# Smartwatch-EXTRA-BOTTOM.net
KiCad netlist of a schematic drawn in EAGLE
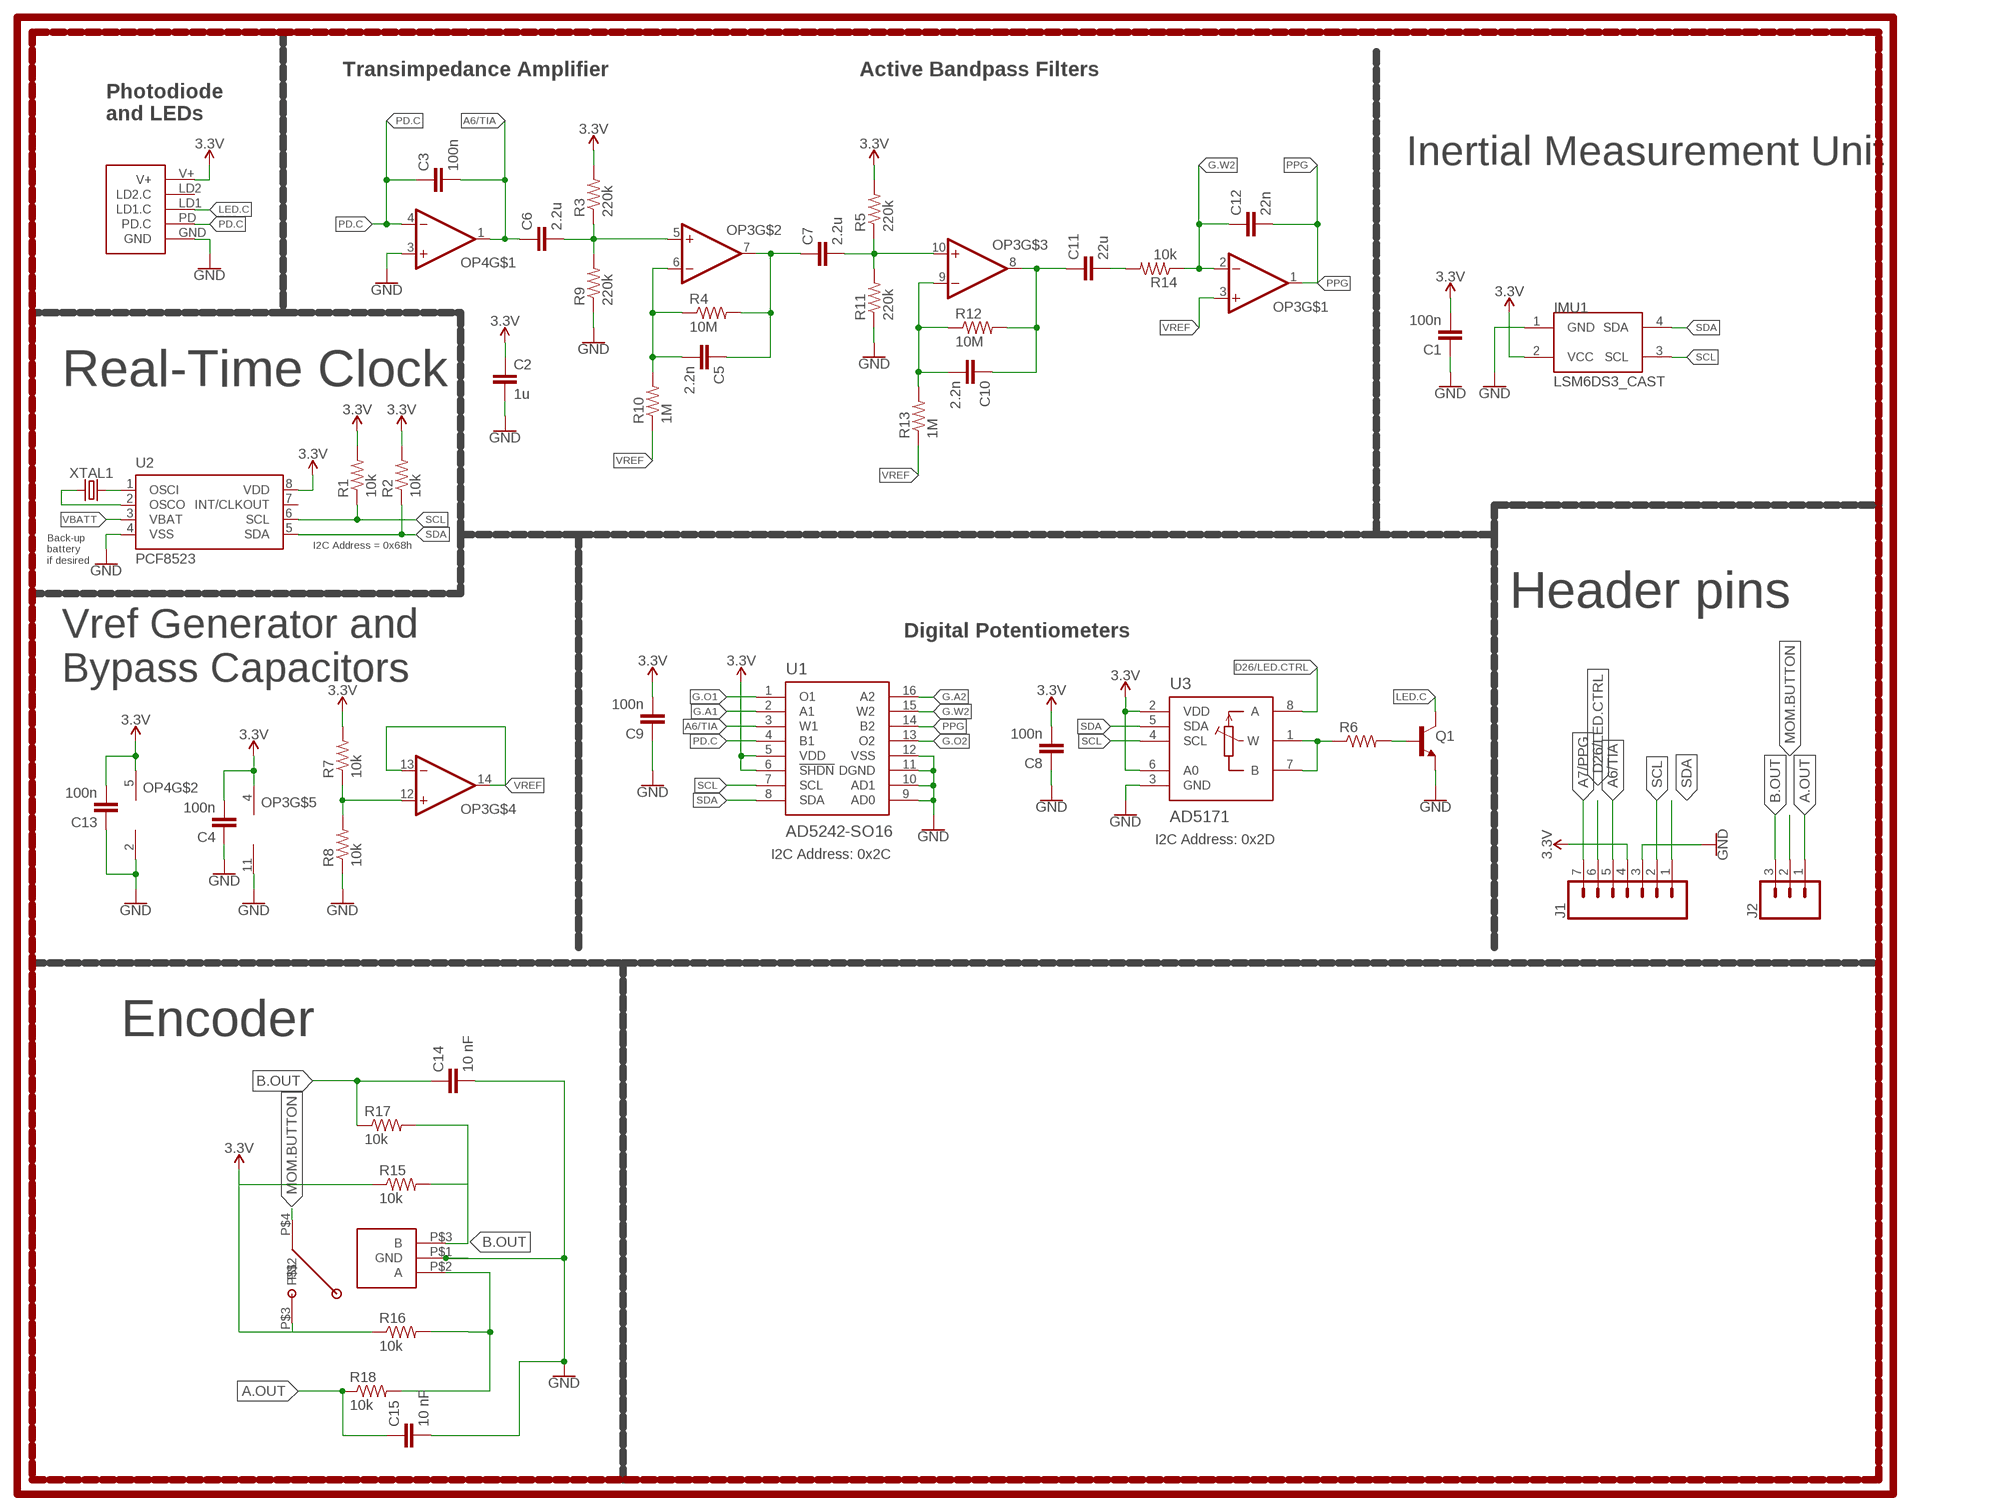
[diagram p0: schematic, sheet 1]

(export (version "E")
  (design (tool "Eeschema 10.0.6"))
  (components
    (comp (ref "B1")
      (value "SWITCH")
      (footprint "eagle-import:SWITCH")
      (libsource (lib "eagle-import") (part "SWITCH"))
    )
    (comp (ref "C1")
      (value "100n")
      (footprint "eagle-import:C0603")
      (libsource (lib "eagle-import") (part "CAPACITOR0603"))
    )
    (comp (ref "C2")
      (value "1u")
      (footprint "eagle-import:C0603")
      (libsource (lib "eagle-import") (part "CAPACITOR0603"))
    )
    (comp (ref "C3")
      (value "100n")
      (footprint "eagle-import:C0603")
      (libsource (lib "eagle-import") (part "CAPACITOR0603"))
    )
    (comp (ref "C4")
      (value "100n")
      (footprint "eagle-import:C0603")
      (libsource (lib "eagle-import") (part "CAPACITOR0603"))
    )
    (comp (ref "C5")
      (value "2.2n")
      (footprint "eagle-import:C0603")
      (libsource (lib "eagle-import") (part "CAPACITOR0603"))
    )
    (comp (ref "C6")
      (value "2.2u")
      (footprint "eagle-import:C0603")
      (libsource (lib "eagle-import") (part "CAPACITOR0603"))
    )
    (comp (ref "C7")
      (value "2.2u")
      (footprint "eagle-import:C0603")
      (libsource (lib "eagle-import") (part "CAPACITOR0603"))
    )
    (comp (ref "C8")
      (value "100n")
      (footprint "eagle-import:C0603")
      (libsource (lib "eagle-import") (part "CAPACITOR0603"))
    )
    (comp (ref "C9")
      (value "100n")
      (footprint "eagle-import:C0603")
      (libsource (lib "eagle-import") (part "CAPACITOR0603"))
    )
    (comp (ref "C10")
      (value "2.2n")
      (footprint "eagle-import:C0603")
      (libsource (lib "eagle-import") (part "CAPACITOR0603"))
    )
    (comp (ref "C11")
      (value "22u")
      (footprint "eagle-import:C0603")
      (libsource (lib "eagle-import") (part "CAPACITOR0603"))
    )
    (comp (ref "C12")
      (value "22n")
      (footprint "eagle-import:C0603")
      (libsource (lib "eagle-import") (part "CAPACITOR0603"))
    )
    (comp (ref "C13")
      (value "100n")
      (footprint "eagle-import:C0603")
      (libsource (lib "eagle-import") (part "CAPACITOR0603"))
    )
    (comp (ref "C14")
      (value "10 nF")
      (footprint "eagle-import:C0603")
      (libsource (lib "eagle-import") (part "CAPACITOR0603"))
    )
    (comp (ref "C15")
      (value "10 nF")
      (footprint "eagle-import:C0603")
      (libsource (lib "eagle-import") (part "CAPACITOR0603"))
    )
    (comp (ref "ENC1")
      (value "EVQVU")
      (footprint "eagle-import:EVQVU")
      (libsource (lib "eagle-import") (part "EVQVU"))
    )
    (comp (ref "IMU1")
      (value "LSM6DS3_CAST")
      (footprint "eagle-import:LSM6DS3_CAST")
      (libsource (lib "eagle-import") (part "LSM6DS3_CAST"))
    )
    (comp (ref "J1")
      (value "CONN_07-1.27MM")
      (footprint "eagle-import:1X07_1.27MM")
      (libsource (lib "eagle-import") (part "CONN_07-1.27MM"))
    )
    (comp (ref "J2")
      (value "CONN_03.50MIL")
      (footprint "eagle-import:1X03_1.27MM")
      (libsource (lib "eagle-import") (part "CONN_03.50MIL"))
    )
    (comp (ref "OP3")
      (value "OP-QUAD-SO14")
      (footprint "eagle-import:SO14")
      (libsource (lib "eagle-import") (part "OP-QUAD-SO14"))
    )
    (comp (ref "OP4")
      (value "OP-SINGLEOT")
      (footprint "eagle-import:SOT23-5")
      (libsource (lib "eagle-import") (part "OP-SINGLEOT"))
    )
    (comp (ref "Q1")
      (value "NPN-GENERIC")
      (footprint "eagle-import:SOT23-3")
      (libsource (lib "eagle-import") (part "NPN-GENERIC"))
    )
    (comp (ref "R1")
      (value "10k")
      (footprint "eagle-import:R0603")
      (libsource (lib "eagle-import") (part "RESISTOR0603"))
    )
    (comp (ref "R2")
      (value "10k")
      (footprint "eagle-import:R0603")
      (libsource (lib "eagle-import") (part "RESISTOR0603"))
    )
    (comp (ref "R3")
      (value "220k")
      (footprint "eagle-import:R0603")
      (libsource (lib "eagle-import") (part "RESISTOR0603"))
    )
    (comp (ref "R4")
      (value "10M")
      (footprint "eagle-import:R0603")
      (libsource (lib "eagle-import") (part "RESISTOR0603"))
    )
    (comp (ref "R5")
      (value "220k")
      (footprint "eagle-import:R0603")
      (libsource (lib "eagle-import") (part "RESISTOR0603"))
    )
    (comp (ref "R6")
      (value "RESISTOR0603")
      (footprint "eagle-import:R0603")
      (libsource (lib "eagle-import") (part "RESISTOR0603"))
    )
    (comp (ref "R7")
      (value "10k")
      (footprint "eagle-import:R0402")
      (libsource (lib "eagle-import") (part "RESISTOR0402"))
    )
    (comp (ref "R8")
      (value "10k")
      (footprint "eagle-import:R0402")
      (libsource (lib "eagle-import") (part "RESISTOR0402"))
    )
    (comp (ref "R9")
      (value "220k")
      (footprint "eagle-import:R0603")
      (libsource (lib "eagle-import") (part "RESISTOR0603"))
    )
    (comp (ref "R10")
      (value "1M")
      (footprint "eagle-import:R0603")
      (libsource (lib "eagle-import") (part "RESISTOR0603"))
    )
    (comp (ref "R11")
      (value "220k")
      (footprint "eagle-import:R0603")
      (libsource (lib "eagle-import") (part "RESISTOR0603"))
    )
    (comp (ref "R12")
      (value "10M")
      (footprint "eagle-import:R0603")
      (libsource (lib "eagle-import") (part "RESISTOR0603"))
    )
    (comp (ref "R13")
      (value "1M")
      (footprint "eagle-import:R0603")
      (libsource (lib "eagle-import") (part "RESISTOR0603"))
    )
    (comp (ref "R14")
      (value "10k")
      (footprint "eagle-import:R0603")
      (libsource (lib "eagle-import") (part "RESISTOR0603"))
    )
    (comp (ref "R15")
      (value "10k")
      (footprint "eagle-import:R0603")
      (libsource (lib "eagle-import") (part "RESISTOR0603"))
    )
    (comp (ref "R16")
      (value "10k")
      (footprint "eagle-import:R0603")
      (libsource (lib "eagle-import") (part "RESISTOR0603"))
    )
    (comp (ref "R17")
      (value "10k")
      (footprint "eagle-import:R0603")
      (libsource (lib "eagle-import") (part "RESISTOR0603"))
    )
    (comp (ref "R18")
      (value "10k")
      (footprint "eagle-import:R0603")
      (libsource (lib "eagle-import") (part "RESISTOR0603"))
    )
    (comp (ref "U1")
      (value "AD5242-SO16")
      (footprint "eagle-import:SO16")
      (libsource (lib "eagle-import") (part "AD5242-SO16"))
    )
    (comp (ref "U2")
      (value "PCF8523")
      (footprint "eagle-import:SO8")
      (libsource (lib "eagle-import") (part "PCF8523"))
    )
    (comp (ref "U3")
      (value "AD5171")
      (footprint "eagle-import:SOT-23-8")
      (libsource (lib "eagle-import") (part "AD5171"))
    )
    (comp (ref "U4")
      (value "PPG.MODULE.2")
      (footprint "eagle-import:PPG.MODULE.2")
      (libsource (lib "eagle-import") (part "PPG.MODULE.2"))
    )
    (comp (ref "XTAL1")
      (value "32.7680kHz")
      (footprint "eagle-import:2-SMD.NOLEAD.2.0MMTO1.2MM")
      (fields (field (name "FREQ") "32.7680KHZ"))
      (libsource (lib "eagle-import") (part "CRYSTALECS-.327-12.5-12-C-TR"))
    )
  )
  (nets
    (net (code "1") (name "3.3V") (class "Default")
      (node (ref "B1") (pin "P$3") (pinfunction "P$2_P$3") (pintype "bidirectional"))
      (node (ref "C1") (pin "2") (pinfunction "2_2") (pintype "passive"))
      (node (ref "C13") (pin "2") (pinfunction "2_2") (pintype "passive"))
      (node (ref "C2") (pin "1") (pinfunction "1_1") (pintype "passive"))
      (node (ref "C4") (pin "2") (pinfunction "2_2") (pintype "passive"))
      (node (ref "C8") (pin "2") (pinfunction "2_2") (pintype "passive"))
      (node (ref "C9") (pin "2") (pinfunction "2_2") (pintype "passive"))
      (node (ref "IMU1") (pin "2") (pinfunction "VCC_2") (pintype "bidirectional"))
      (node (ref "J1") (pin "4") (pinfunction "4_4") (pintype "passive"))
      (node (ref "OP3") (pin "4") (pinfunction "V+_4") (pintype "power_in"))
      (node (ref "OP4") (pin "5") (pinfunction "V+_5") (pintype "power_in"))
      (node (ref "R1") (pin "2") (pinfunction "2_2") (pintype "passive"))
      (node (ref "R15") (pin "1") (pinfunction "1_1") (pintype "passive"))
      (node (ref "R16") (pin "1") (pinfunction "1_1") (pintype "passive"))
      (node (ref "R2") (pin "2") (pinfunction "2_2") (pintype "passive"))
      (node (ref "R3") (pin "2") (pinfunction "2_2") (pintype "passive"))
      (node (ref "R5") (pin "2") (pinfunction "2_2") (pintype "passive"))
      (node (ref "R7") (pin "2") (pinfunction "2_2") (pintype "passive"))
      (node (ref "U1") (pin "5") (pinfunction "VDD_5") (pintype "bidirectional"))
      (node (ref "U1") (pin "6") (pinfunction "~{SHDN}_6") (pintype "bidirectional"))
      (node (ref "U2") (pin "8") (pinfunction "VDD_8") (pintype "power_in"))
      (node (ref "U3") (pin "2") (pinfunction "VDD_2") (pintype "bidirectional"))
      (node (ref "U3") (pin "6") (pinfunction "A0_6") (pintype "bidirectional"))
      (node (ref "U4") (pin "V+") (pinfunction "V+_V+") (pintype "bidirectional"))
    )
    (net (code "2") (name "A.OUT") (class "Default")
      (node (ref "C15") (pin "1") (pinfunction "1_1") (pintype "passive"))
      (node (ref "ENC1") (pin "P$2") (pinfunction "A_P$2") (pintype "bidirectional"))
      (node (ref "J2") (pin "1") (pinfunction "1_1") (pintype "passive"))
      (node (ref "R16") (pin "2") (pinfunction "2_2") (pintype "passive"))
      (node (ref "R18") (pin "1") (pinfunction "1_1") (pintype "passive"))
      (node (ref "R18") (pin "2") (pinfunction "2_2") (pintype "passive"))
    )
    (net (code "3") (name "A6{slash}TIA") (class "Default")
      (node (ref "C3") (pin "2") (pinfunction "2_2") (pintype "passive"))
      (node (ref "C6") (pin "1") (pinfunction "1_1") (pintype "passive"))
      (node (ref "J1") (pin "5") (pinfunction "5_5") (pintype "passive"))
      (node (ref "OP4") (pin "1") (pinfunction "OUT_1") (pintype "output"))
      (node (ref "U1") (pin "3") (pinfunction "W1_3") (pintype "bidirectional"))
    )
    (net (code "4") (name "A7{slash}PPG") (class "Default")
      (node (ref "J1") (pin "7") (pinfunction "7_7") (pintype "passive"))
    )
    (net (code "5") (name "B.OUT") (class "Default")
      (node (ref "C14") (pin "1") (pinfunction "1_1") (pintype "passive"))
      (node (ref "ENC1") (pin "P$3") (pinfunction "B_P$3") (pintype "bidirectional"))
      (node (ref "J2") (pin "3") (pinfunction "3_3") (pintype "passive"))
      (node (ref "R17") (pin "1") (pinfunction "1_1") (pintype "passive"))
    )
    (net (code "6") (name "D26{slash}LED.CTRL") (class "Default")
      (node (ref "J1") (pin "6") (pinfunction "6_6") (pintype "passive"))
      (node (ref "U3") (pin "8") (pinfunction "A_8") (pintype "bidirectional"))
    )
    (net (code "7") (name "G.A1") (class "Default")
      (node (ref "U1") (pin "2") (pinfunction "A1_2") (pintype "bidirectional"))
    )
    (net (code "8") (name "G.A2") (class "Default")
      (node (ref "U1") (pin "16") (pinfunction "A2_16") (pintype "bidirectional"))
    )
    (net (code "9") (name "G.O1") (class "Default")
      (node (ref "U1") (pin "1") (pinfunction "O1_1") (pintype "bidirectional"))
    )
    (net (code "10") (name "G.O2") (class "Default")
      (node (ref "U1") (pin "13") (pinfunction "O2_13") (pintype "bidirectional"))
    )
    (net (code "11") (name "G.W2") (class "Default")
      (node (ref "C12") (pin "1") (pinfunction "1_1") (pintype "passive"))
      (node (ref "OP3") (pin "2") (pinfunction "-IN_2") (pintype "input"))
      (node (ref "R14") (pin "1") (pinfunction "1_1") (pintype "passive"))
      (node (ref "U1") (pin "15") (pinfunction "W2_15") (pintype "bidirectional"))
    )
    (net (code "12") (name "GND") (class "Default")
      (node (ref "C1") (pin "1") (pinfunction "1_1") (pintype "passive"))
      (node (ref "C13") (pin "1") (pinfunction "1_1") (pintype "passive"))
      (node (ref "C14") (pin "2") (pinfunction "2_2") (pintype "passive"))
      (node (ref "C15") (pin "2") (pinfunction "2_2") (pintype "passive"))
      (node (ref "C2") (pin "2") (pinfunction "2_2") (pintype "passive"))
      (node (ref "C4") (pin "1") (pinfunction "1_1") (pintype "passive"))
      (node (ref "C8") (pin "1") (pinfunction "1_1") (pintype "passive"))
      (node (ref "C9") (pin "1") (pinfunction "1_1") (pintype "passive"))
      (node (ref "ENC1") (pin "P$1") (pinfunction "GND_P$1") (pintype "bidirectional"))
      (node (ref "IMU1") (pin "1") (pinfunction "GND_1") (pintype "bidirectional"))
      (node (ref "J1") (pin "3") (pinfunction "3_3") (pintype "passive"))
      (node (ref "OP3") (pin "11") (pinfunction "V-_11") (pintype "power_in"))
      (node (ref "OP4") (pin "2") (pinfunction "V-_2") (pintype "power_in"))
      (node (ref "OP4") (pin "3") (pinfunction "+IN_3") (pintype "input"))
      (node (ref "Q1") (pin "2") (pinfunction "E_2") (pintype "passive"))
      (node (ref "R11") (pin "1") (pinfunction "1_1") (pintype "passive"))
      (node (ref "R8") (pin "1") (pinfunction "1_1") (pintype "passive"))
      (node (ref "R9") (pin "1") (pinfunction "1_1") (pintype "passive"))
      (node (ref "U1") (pin "10") (pinfunction "AD1_10") (pintype "bidirectional"))
      (node (ref "U1") (pin "11") (pinfunction "DGND_11") (pintype "bidirectional"))
      (node (ref "U1") (pin "12") (pinfunction "VSS_12") (pintype "bidirectional"))
      (node (ref "U1") (pin "9") (pinfunction "AD0_9") (pintype "bidirectional"))
      (node (ref "U2") (pin "4") (pinfunction "VSS_4") (pintype "power_in"))
      (node (ref "U3") (pin "3") (pinfunction "GND_3") (pintype "bidirectional"))
      (node (ref "U4") (pin "GND") (pinfunction "GND_GND") (pintype "bidirectional"))
    )
    (net (code "13") (name "LED.C") (class "Default")
      (node (ref "Q1") (pin "3") (pinfunction "C_3") (pintype "passive"))
      (node (ref "U4") (pin "LD1") (pinfunction "LD1.C_LD1") (pintype "bidirectional"))
    )
    (net (code "14") (name "MOM.BUTTON") (class "Default")
      (node (ref "B1") (pin "P$4") (pinfunction "P$1_P$4") (pintype "bidirectional"))
      (node (ref "J2") (pin "2") (pinfunction "2_2") (pintype "passive"))
    )
    (net (code "15") (name "Net-(C11-Pad2)") (class "Default")
      (node (ref "C11") (pin "2") (pinfunction "2_2") (pintype "passive"))
      (node (ref "R14") (pin "2") (pinfunction "2_2") (pintype "passive"))
    )
    (net (code "16") (name "Net-(OP3B-+IN)") (class "Default")
      (node (ref "C6") (pin "2") (pinfunction "2_2") (pintype "passive"))
      (node (ref "OP3") (pin "5") (pinfunction "+IN_5") (pintype "input"))
      (node (ref "R3") (pin "1") (pinfunction "1_1") (pintype "passive"))
      (node (ref "R9") (pin "2") (pinfunction "2_2") (pintype "passive"))
    )
    (net (code "17") (name "Net-(OP3B--IN)") (class "Default")
      (node (ref "C5") (pin "2") (pinfunction "2_2") (pintype "passive"))
      (node (ref "OP3") (pin "6") (pinfunction "-IN_6") (pintype "input"))
      (node (ref "R10") (pin "2") (pinfunction "2_2") (pintype "passive"))
      (node (ref "R4") (pin "1") (pinfunction "1_1") (pintype "passive"))
    )
    (net (code "18") (name "Net-(OP3B-OUT)") (class "Default")
      (node (ref "C5") (pin "1") (pinfunction "1_1") (pintype "passive"))
      (node (ref "C7") (pin "1") (pinfunction "1_1") (pintype "passive"))
      (node (ref "OP3") (pin "7") (pinfunction "OUT_7") (pintype "output"))
      (node (ref "R4") (pin "2") (pinfunction "2_2") (pintype "passive"))
    )
    (net (code "19") (name "Net-(OP3C-+IN)") (class "Default")
      (node (ref "C7") (pin "2") (pinfunction "2_2") (pintype "passive"))
      (node (ref "OP3") (pin "10") (pinfunction "+IN_10") (pintype "input"))
      (node (ref "R11") (pin "2") (pinfunction "2_2") (pintype "passive"))
      (node (ref "R5") (pin "1") (pinfunction "1_1") (pintype "passive"))
    )
    (net (code "20") (name "Net-(OP3C--IN)") (class "Default")
      (node (ref "C10") (pin "2") (pinfunction "2_2") (pintype "passive"))
      (node (ref "OP3") (pin "9") (pinfunction "-IN_9") (pintype "input"))
      (node (ref "R12") (pin "1") (pinfunction "1_1") (pintype "passive"))
      (node (ref "R13") (pin "2") (pinfunction "2_2") (pintype "passive"))
    )
    (net (code "21") (name "Net-(OP3C-OUT)") (class "Default")
      (node (ref "C10") (pin "1") (pinfunction "1_1") (pintype "passive"))
      (node (ref "C11") (pin "1") (pinfunction "1_1") (pintype "passive"))
      (node (ref "OP3") (pin "8") (pinfunction "OUT_8") (pintype "output"))
      (node (ref "R12") (pin "2") (pinfunction "2_2") (pintype "passive"))
    )
    (net (code "22") (name "Net-(OP3D-+IN)") (class "Default")
      (node (ref "OP3") (pin "12") (pinfunction "+IN_12") (pintype "input"))
      (node (ref "R7") (pin "1") (pinfunction "1_1") (pintype "passive"))
      (node (ref "R8") (pin "2") (pinfunction "2_2") (pintype "passive"))
    )
    (net (code "23") (name "Net-(Q1-B)") (class "Default")
      (node (ref "Q1") (pin "1") (pinfunction "B_1") (pintype "passive"))
      (node (ref "R6") (pin "2") (pinfunction "2_2") (pintype "passive"))
    )
    (net (code "24") (name "Net-(R15-Pad2)") (class "Default")
      (node (ref "R15") (pin "2") (pinfunction "2_2") (pintype "passive"))
      (node (ref "R17") (pin "2") (pinfunction "2_2") (pintype "passive"))
    )
    (net (code "25") (name "Net-(U2-OSCI)") (class "Default")
      (node (ref "U2") (pin "1") (pinfunction "OSCI_1") (pintype "bidirectional"))
      (node (ref "XTAL1") (pin "P$2") (pinfunction "2_P$2") (pintype "passive"))
    )
    (net (code "26") (name "Net-(U2-OSCO)") (class "Default")
      (node (ref "U2") (pin "2") (pinfunction "OSCO_2") (pintype "bidirectional"))
      (node (ref "XTAL1") (pin "P$1") (pinfunction "1_P$1") (pintype "passive"))
    )
    (net (code "27") (name "Net-(U3-B)") (class "Default")
      (node (ref "R6") (pin "1") (pinfunction "1_1") (pintype "passive"))
      (node (ref "U3") (pin "1") (pinfunction "W_1") (pintype "bidirectional"))
      (node (ref "U3") (pin "7") (pinfunction "B_7") (pintype "bidirectional"))
    )
    (net (code "28") (name "PD.C") (class "Default")
      (node (ref "C3") (pin "1") (pinfunction "1_1") (pintype "passive"))
      (node (ref "OP4") (pin "4") (pinfunction "-IN_4") (pintype "input"))
      (node (ref "U1") (pin "4") (pinfunction "B1_4") (pintype "bidirectional"))
      (node (ref "U4") (pin "PD") (pinfunction "PD.C_PD") (pintype "bidirectional"))
    )
    (net (code "29") (name "PPG") (class "Default")
      (node (ref "C12") (pin "2") (pinfunction "2_2") (pintype "passive"))
      (node (ref "OP3") (pin "1") (pinfunction "OUT_1") (pintype "output"))
      (node (ref "U1") (pin "14") (pinfunction "B2_14") (pintype "bidirectional"))
    )
    (net (code "30") (name "SCL") (class "Default")
      (node (ref "IMU1") (pin "3") (pinfunction "SCL_3") (pintype "bidirectional"))
      (node (ref "J1") (pin "2") (pinfunction "2_2") (pintype "passive"))
      (node (ref "R1") (pin "1") (pinfunction "1_1") (pintype "passive"))
      (node (ref "U1") (pin "7") (pinfunction "SCL_7") (pintype "bidirectional"))
      (node (ref "U2") (pin "6") (pinfunction "SCL_6") (pintype "bidirectional"))
      (node (ref "U3") (pin "4") (pinfunction "SCL_4") (pintype "bidirectional"))
    )
    (net (code "31") (name "SDA") (class "Default")
      (node (ref "IMU1") (pin "4") (pinfunction "SDA_4") (pintype "bidirectional"))
      (node (ref "J1") (pin "1") (pinfunction "1_1") (pintype "passive"))
      (node (ref "R2") (pin "1") (pinfunction "1_1") (pintype "passive"))
      (node (ref "U1") (pin "8") (pinfunction "SDA_8") (pintype "bidirectional"))
      (node (ref "U2") (pin "5") (pinfunction "SDA_5") (pintype "bidirectional"))
      (node (ref "U3") (pin "5") (pinfunction "SDA_5") (pintype "bidirectional"))
    )
    (net (code "32") (name "VBATT") (class "Default")
      (node (ref "U2") (pin "3") (pinfunction "VBAT_3") (pintype "power_in"))
    )
    (net (code "33") (name "VREF") (class "Default")
      (node (ref "OP3") (pin "13") (pinfunction "-IN_13") (pintype "input"))
      (node (ref "OP3") (pin "14") (pinfunction "OUT_14") (pintype "output"))
      (node (ref "OP3") (pin "3") (pinfunction "+IN_3") (pintype "input"))
      (node (ref "R10") (pin "1") (pinfunction "1_1") (pintype "passive"))
      (node (ref "R13") (pin "1") (pinfunction "1_1") (pintype "passive"))
    )
    (net (code "34") (name "unconnected-(U2-INT{slash}CLKOUT-Pad7)") (class "Default")
      (node (ref "U2") (pin "7") (pinfunction "INT/CLKOUT_7") (pintype "bidirectional"))
    )
    (net (code "35") (name "unconnected-(U4-LD2.C-PadLD2)") (class "Default")
      (node (ref "U4") (pin "LD2") (pinfunction "LD2.C_LD2") (pintype "bidirectional"))
    )
  )
)
